# V2a.net
KiCad netlist of a schematic drawn in EAGLE
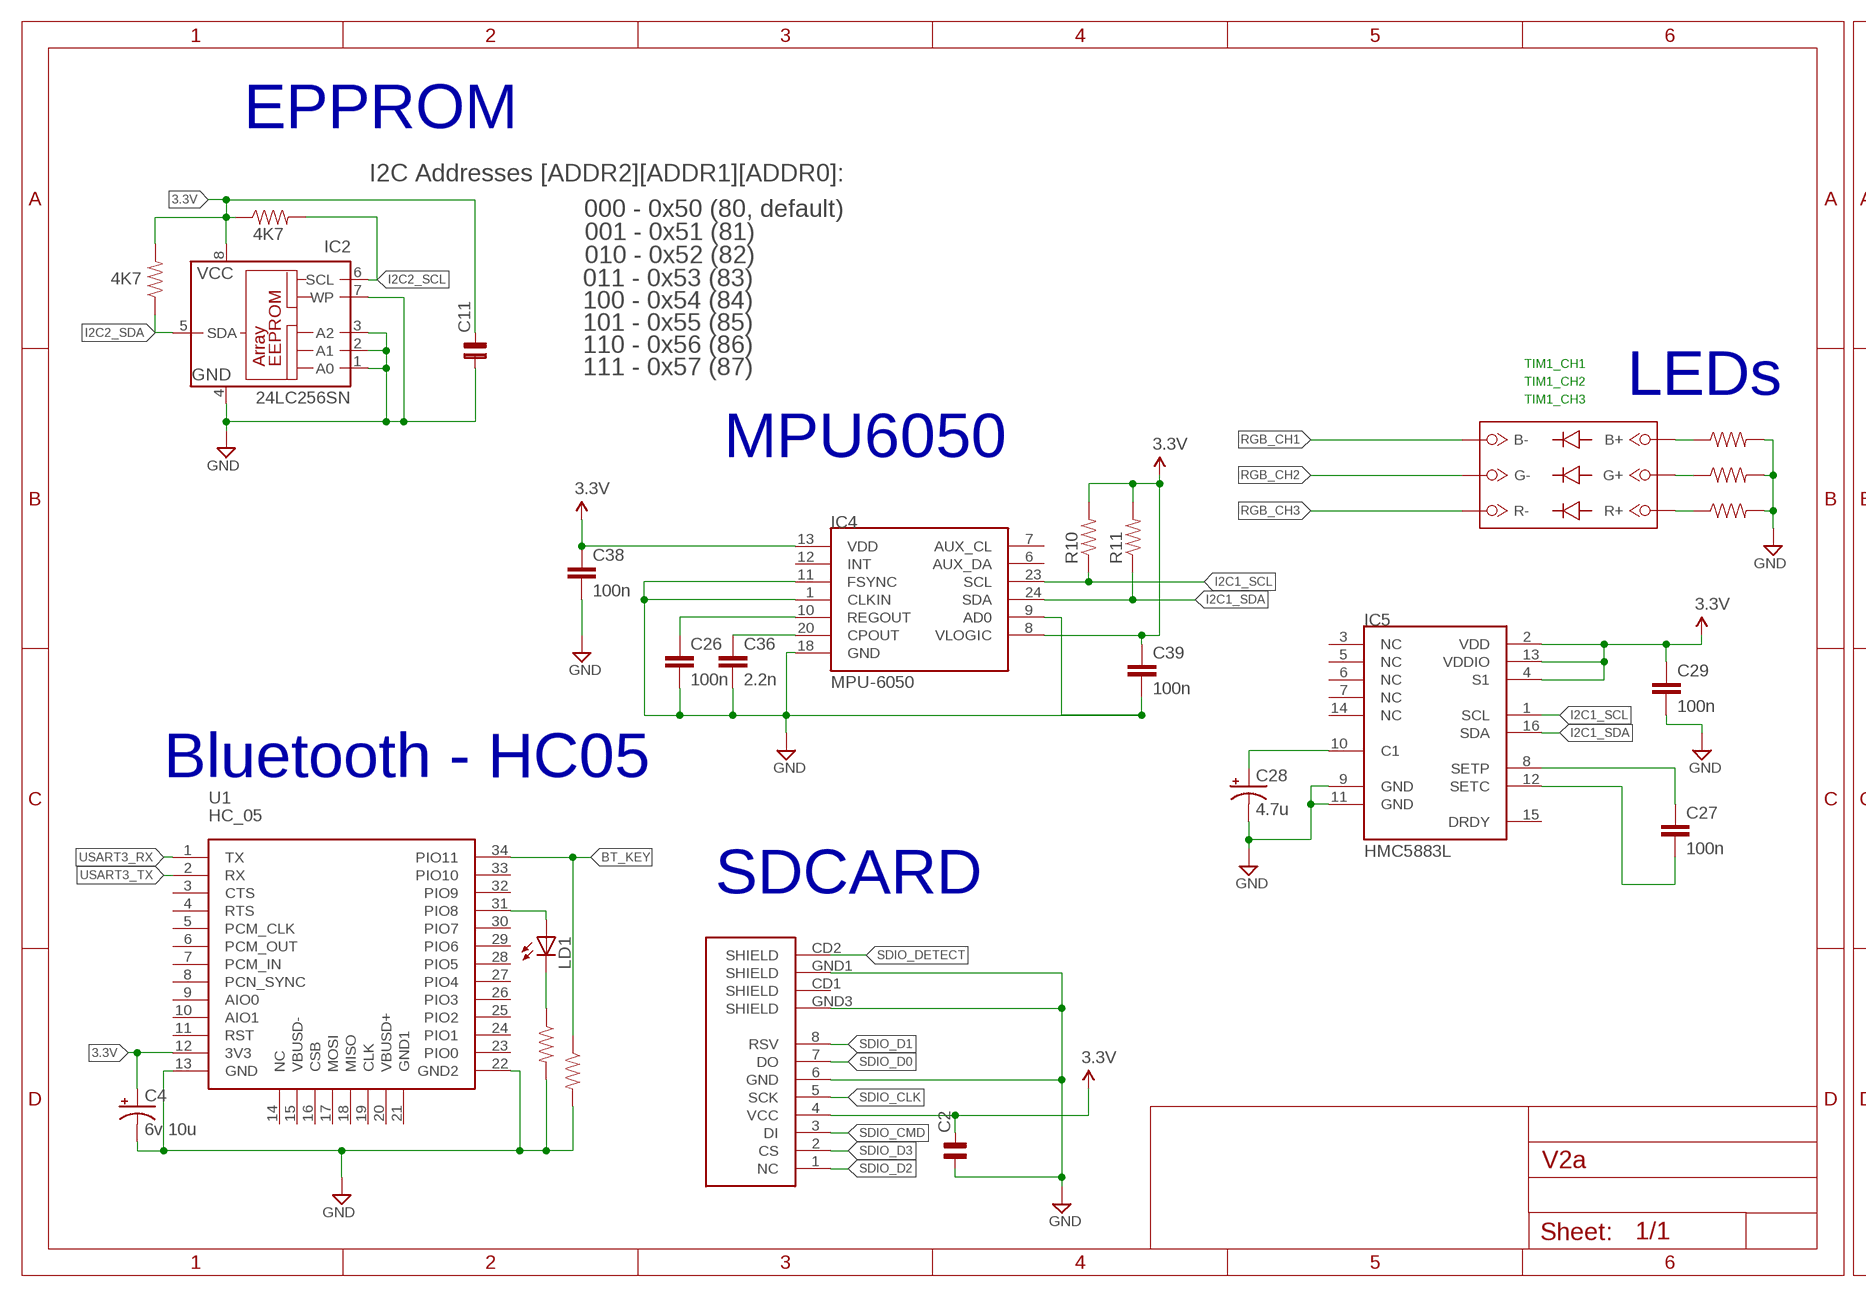
[diagram p0: schematic, sheet 1, part 1 of 2]
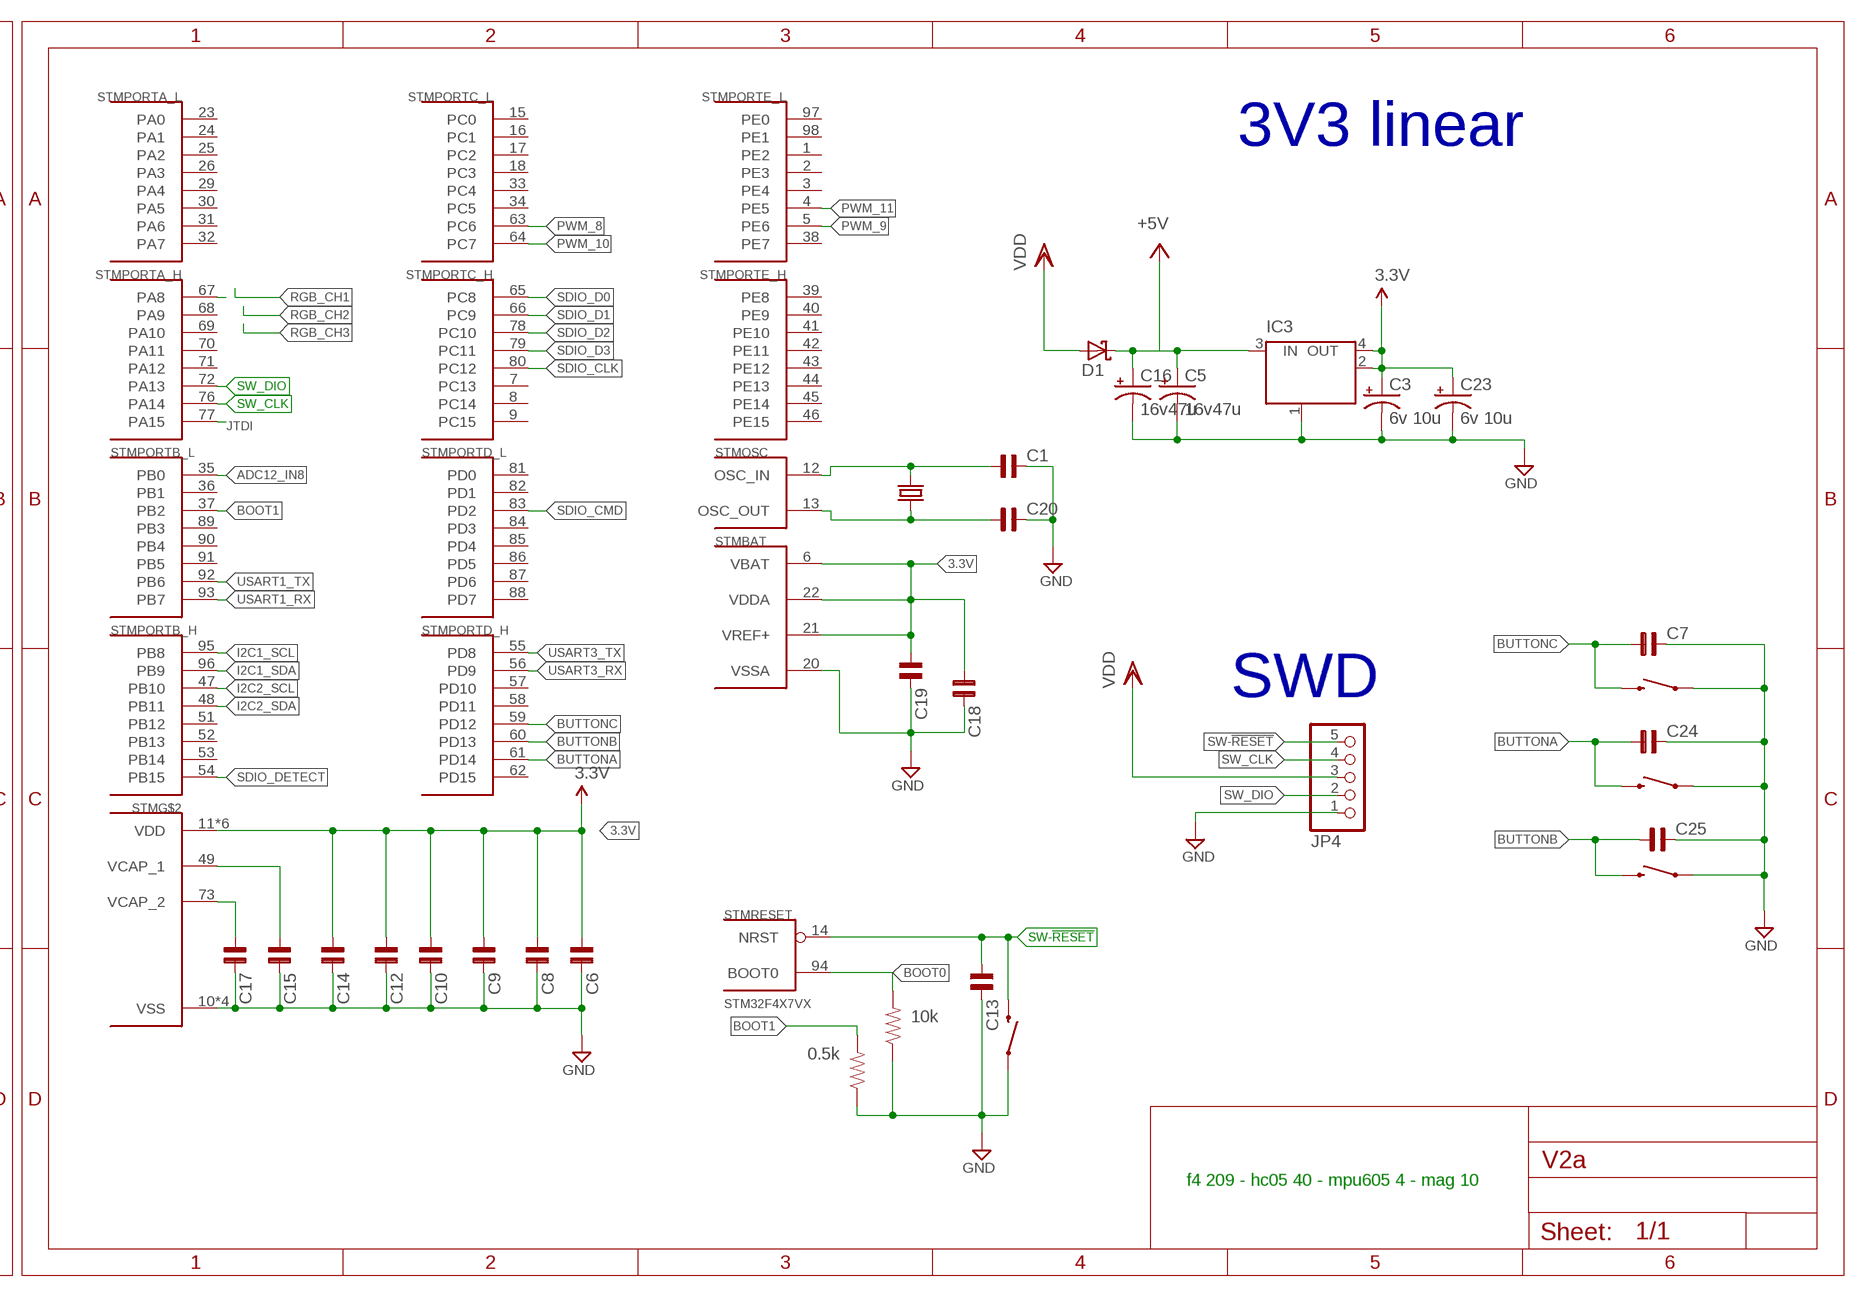
[diagram p1: schematic, sheet 1, part 2 of 2]

(export (version "E")
  (design (tool "Eeschema 10.0.6"))
  (components
    (comp (ref "C1")
      (value "C-NP-SMD-0603")
      (footprint "eagle-import:C-0603")
      (libsource (lib "eagle-import") (part "C-NP-SMD-0603"))
    )
    (comp (ref "C2")
      (value "C-NP-SMD-0603")
      (footprint "eagle-import:C-0603")
      (libsource (lib "eagle-import") (part "C-NP-SMD-0603"))
    )
    (comp (ref "C3")
      (value "6v 10u")
      (footprint "eagle-import:SMC_C")
      (libsource (lib "eagle-import") (part "CPOL-USSMCC"))
    )
    (comp (ref "C4")
      (value "6v 10u")
      (footprint "eagle-import:SMC_A")
      (libsource (lib "eagle-import") (part "CPOL-USSMCA"))
    )
    (comp (ref "C5")
      (value "16v47u")
      (footprint "eagle-import:SMC_C")
      (libsource (lib "eagle-import") (part "CPOL-USSMCC"))
    )
    (comp (ref "C6")
      (value "C-NP-SMD-0603")
      (footprint "eagle-import:C-0603")
      (libsource (lib "eagle-import") (part "C-NP-SMD-0603"))
    )
    (comp (ref "C7")
      (value "C-NP-SMD-0603")
      (footprint "eagle-import:C-0603")
      (libsource (lib "eagle-import") (part "C-NP-SMD-0603"))
    )
    (comp (ref "C8")
      (value "C-NP-SMD-0603")
      (footprint "eagle-import:C-0603")
      (libsource (lib "eagle-import") (part "C-NP-SMD-0603"))
    )
    (comp (ref "C9")
      (value "C-NP-SMD-0603")
      (footprint "eagle-import:C-0603")
      (libsource (lib "eagle-import") (part "C-NP-SMD-0603"))
    )
    (comp (ref "C10")
      (value "C-NP-SMD-0603")
      (footprint "eagle-import:C-0603")
      (libsource (lib "eagle-import") (part "C-NP-SMD-0603"))
    )
    (comp (ref "C11")
      (value "C-NP-SMD-0603")
      (footprint "eagle-import:C-0603")
      (libsource (lib "eagle-import") (part "C-NP-SMD-0603"))
    )
    (comp (ref "C12")
      (value "C-NP-SMD-0603")
      (footprint "eagle-import:C-0603")
      (libsource (lib "eagle-import") (part "C-NP-SMD-0603"))
    )
    (comp (ref "C13")
      (value "C-NP-SMD-0603")
      (footprint "eagle-import:C-0603")
      (libsource (lib "eagle-import") (part "C-NP-SMD-0603"))
    )
    (comp (ref "C14")
      (value "C-NP-SMD-0603")
      (footprint "eagle-import:C-0603")
      (libsource (lib "eagle-import") (part "C-NP-SMD-0603"))
    )
    (comp (ref "C15")
      (value "C-NP-SMD-0603")
      (footprint "eagle-import:C-0603")
      (libsource (lib "eagle-import") (part "C-NP-SMD-0603"))
    )
    (comp (ref "C16")
      (value "16v47u")
      (footprint "eagle-import:SMC_C")
      (libsource (lib "eagle-import") (part "CPOL-USSMCC"))
    )
    (comp (ref "C17")
      (value "C-NP-SMD-0603")
      (footprint "eagle-import:C-0603")
      (libsource (lib "eagle-import") (part "C-NP-SMD-0603"))
    )
    (comp (ref "C18")
      (value "C-NP-SMD-0603")
      (footprint "eagle-import:C-0603")
      (libsource (lib "eagle-import") (part "C-NP-SMD-0603"))
    )
    (comp (ref "C19")
      (value "C-NP-SMD-0603")
      (footprint "eagle-import:C-0603")
      (libsource (lib "eagle-import") (part "C-NP-SMD-0603"))
    )
    (comp (ref "C20")
      (value "C-NP-SMD-0603")
      (footprint "eagle-import:C-0603")
      (libsource (lib "eagle-import") (part "C-NP-SMD-0603"))
    )
    (comp (ref "C23")
      (value "6v 10u")
      (footprint "eagle-import:SMC_C")
      (libsource (lib "eagle-import") (part "CPOL-USSMCC"))
    )
    (comp (ref "C24")
      (value "C-NP-SMD-0603")
      (footprint "eagle-import:C-0603")
      (libsource (lib "eagle-import") (part "C-NP-SMD-0603"))
    )
    (comp (ref "C25")
      (value "C-NP-SMD-0603")
      (footprint "eagle-import:C-0603")
      (libsource (lib "eagle-import") (part "C-NP-SMD-0603"))
    )
    (comp (ref "C26")
      (value "100n")
      (footprint "eagle-import:SPARKFUN_0603-CAP")
      (libsource (lib "eagle-import") (part "SPARKFUN_CAP0603-CAP"))
    )
    (comp (ref "C27")
      (value "100n")
      (footprint "eagle-import:SPARKFUN_0603-CAP")
      (libsource (lib "eagle-import") (part "SPARKFUN_CAP0603-CAP"))
    )
    (comp (ref "C28")
      (value "4.7u")
      (footprint "eagle-import:SMC_A")
      (libsource (lib "eagle-import") (part "CPOL-USSMCA"))
    )
    (comp (ref "C29")
      (value "100n")
      (footprint "eagle-import:SPARKFUN_0603-CAP")
      (libsource (lib "eagle-import") (part "SPARKFUN_CAP0603-CAP"))
    )
    (comp (ref "C36")
      (value "2.2n")
      (footprint "eagle-import:SPARKFUN_0603-CAP")
      (libsource (lib "eagle-import") (part "SPARKFUN_CAP0603-CAP"))
    )
    (comp (ref "C38")
      (value "100n")
      (footprint "eagle-import:SPARKFUN_0603-CAP")
      (libsource (lib "eagle-import") (part "SPARKFUN_CAP0603-CAP"))
    )
    (comp (ref "C39")
      (value "100n")
      (footprint "eagle-import:SPARKFUN_0603-CAP")
      (libsource (lib "eagle-import") (part "SPARKFUN_CAP0603-CAP"))
    )
    (comp (ref "D1")
      (value "MBRS330T3")
      (footprint "eagle-import:SMC")
      (libsource (lib "eagle-import") (part "MBRS30T33"))
    )
    (comp (ref "IC2")
      (value "24LC256SN")
      (footprint "eagle-import:SO-08")
      (fields (field (name "MF") "MICROCHIP") (field (name "MPN") "24LC256-I/SN"))
      (libsource (lib "eagle-import") (part "24SNLC256"))
    )
    (comp (ref "IC3")
      (value "LINEAR_MC33269ST-3.3T3")
      (footprint "eagle-import:LINEAR_SOT223")
      (libsource (lib "eagle-import") (part "LINEAR_MC33269ST-3.3T3"))
    )
    (comp (ref "IC4")
      (value "MPU-6050")
      (footprint "eagle-import:TESTING_QFN-24-4MM2")
      (libsource (lib "eagle-import") (part "TESTING_MPU-6050-1"))
    )
    (comp (ref "IC5")
      (value "HMC5883L")
      (footprint "eagle-import:SPARKFUN_16LPCC")
      (libsource (lib "eagle-import") (part "SPARKFUN_HMC5883LSMD"))
    )
    (comp (ref "JP4")
      (value "PINHD-1X5_2.54-90°")
      (footprint "eagle-import:1X05_90")
      (libsource (lib "eagle-import") (part "PINHD-1X5_2.54-90°"))
    )
    (comp (ref "LD1")
      (value "LEDCHIPLED_0603")
      (footprint "eagle-import:CHIPLED_0603")
      (libsource (lib "eagle-import") (part "LEDCHIPLED_0603"))
    )
    (comp (ref "R2")
      (value "10K")
      (footprint "eagle-import:SPARKFUN_0603-RES")
      (libsource (lib "eagle-import") (part "Robotech_RCL_SPARKFUN_RESISTOR0603-RES"))
    )
    (comp (ref "R3")
      (value "10K")
      (footprint "eagle-import:SPARKFUN_0603-RES")
      (libsource (lib "eagle-import") (part "Robotech_RCL_SPARKFUN_RESISTOR0603-RES"))
    )
    (comp (ref "R5")
      (value "10K")
      (footprint "eagle-import:SPARKFUN_0603-RES")
      (libsource (lib "eagle-import") (part "Robotech_RCL_SPARKFUN_RESISTOR0603-RES"))
    )
    (comp (ref "R6")
      (value "10K")
      (footprint "eagle-import:SPARKFUN_0603-RES")
      (libsource (lib "eagle-import") (part "Robotech_RCL_SPARKFUN_RESISTOR0603-RES"))
    )
    (comp (ref "R7")
      (value "10k")
      (footprint "eagle-import:SPARKFUN_0603-RES")
      (libsource (lib "eagle-import") (part "Robotech_RCL_SPARKFUN_RESISTOR0603-RES"))
    )
    (comp (ref "R8")
      (value "0.5k")
      (footprint "eagle-import:SPARKFUN_0603-RES")
      (libsource (lib "eagle-import") (part "Robotech_RCL_SPARKFUN_RESISTOR0603-RES"))
    )
    (comp (ref "R9")
      (value "10K")
      (footprint "eagle-import:SPARKFUN_0603-RES")
      (libsource (lib "eagle-import") (part "Robotech_RCL_SPARKFUN_RESISTOR0603-RES"))
    )
    (comp (ref "R10")
      (value "SPARKFUN_RESISTOR0603-RES")
      (footprint "eagle-import:SPARKFUN_0603-RES")
      (libsource (lib "eagle-import") (part "SPARKFUN_RESISTOR0603-RES"))
    )
    (comp (ref "R11")
      (value "SPARKFUN_RESISTOR0603-RES")
      (footprint "eagle-import:SPARKFUN_0603-RES")
      (libsource (lib "eagle-import") (part "SPARKFUN_RESISTOR0603-RES"))
    )
    (comp (ref "R15")
      (value "4K7")
      (footprint "eagle-import:SPARKFUN_0603-RES")
      (libsource (lib "eagle-import") (part "Robotech_RCL_SPARKFUN_RESISTOR0603-RES"))
    )
    (comp (ref "R16")
      (value "4K7")
      (footprint "eagle-import:SPARKFUN_0603-RES")
      (libsource (lib "eagle-import") (part "Robotech_RCL_SPARKFUN_RESISTOR0603-RES"))
    )
    (comp (ref "S1")
      (value "RESET")
      (footprint "eagle-import:TACTILE-SWITCH-1101NE")
      (fields (field (name "PARTNO") "EVQ-P7J01P"))
      (libsource (lib "eagle-import") (part "SWITCH-MOMENTARY-2-SMD-1101NE"))
    )
    (comp (ref "S2")
      (value "RESET")
      (footprint "eagle-import:TACTILE-SWITCH-1101NE")
      (fields (field (name "PARTNO") "EVQ-P7J01P"))
      (libsource (lib "eagle-import") (part "SWITCH-MOMENTARY-2-SMD-1101NE"))
    )
    (comp (ref "S3")
      (value "RESET")
      (footprint "eagle-import:TACTILE-SWITCH-1101NE")
      (fields (field (name "PARTNO") "EVQ-P7J01P"))
      (libsource (lib "eagle-import") (part "SWITCH-MOMENTARY-2-SMD-1101NE"))
    )
    (comp (ref "S4")
      (value "RESET")
      (footprint "eagle-import:TACTILE-SWITCH-1101NE")
      (fields (field (name "PARTNO") "EVQ-P7J01P"))
      (libsource (lib "eagle-import") (part "SWITCH-MOMENTARY-2-SMD-1101NE"))
    )
    (comp (ref "SDCARD2")
      (value "microSD Socket")
      (footprint "eagle-import:MICRO-SD-SOCKET-PP")
      (libsource (lib "eagle-import") (part "USD-SOCKETNEW"))
    )
    (comp (ref "STM")
      (value "STM32F4X7VX")
      (footprint "eagle-import:TQFP100")
      (fields (field (name "PARTNO") "STM32F427VI"))
      (libsource (lib "eagle-import") (part "STM32F4X7VX"))
    )
    (comp (ref "U$12")
      (value "RGB_LED")
      (footprint "eagle-import:SMD")
      (libsource (lib "eagle-import") (part "RGB_LED"))
    )
    (comp (ref "U1")
      (value "HC_05")
      (footprint "eagle-import:BLUETOOTH_SMD")
      (libsource (lib "eagle-import") (part "HC_05"))
    )
    (comp (ref "Y1")
      (value "CRYSTALHC49US")
      (footprint "eagle-import:HC49US")
      (libsource (lib "eagle-import") (part "CRYSTALHC49US"))
    )
  )
  (nets
    (net (code "1") (name "+5V") (class "Default")
      (node (ref "C16") (pin "+") (pinfunction "+_+") (pintype "passive"))
      (node (ref "C5") (pin "+") (pinfunction "+_+") (pintype "passive"))
      (node (ref "D1") (pin "C") (pinfunction "C_C") (pintype "passive"))
      (node (ref "IC3") (pin "3") (pinfunction "IN_3") (pintype "input"))
    )
    (net (code "2") (name "/JTDI") (class "Default")
      (node (ref "STM") (pin "77") (pinfunction "PA15_77") (pintype "bidirectional"))
    )
    (net (code "3") (name "/SW-~{RESET}") (class "Default")
      (node (ref "C13") (pin "1") (pinfunction "1_1") (pintype "passive"))
      (node (ref "JP4") (pin "5") (pinfunction "5_5") (pintype "passive"))
      (node (ref "S1") (pin "P$2") (pinfunction "2_P$2") (pintype "passive"))
      (node (ref "STM") (pin "14") (pinfunction "NRST_14") (pintype "input"))
    )
    (net (code "4") (name "3.3V") (class "Default")
      (node (ref "C10") (pin "1") (pinfunction "1_1") (pintype "passive"))
      (node (ref "C11") (pin "2") (pinfunction "2_2") (pintype "passive"))
      (node (ref "C12") (pin "1") (pinfunction "1_1") (pintype "passive"))
      (node (ref "C14") (pin "1") (pinfunction "1_1") (pintype "passive"))
      (node (ref "C18") (pin "1") (pinfunction "1_1") (pintype "passive"))
      (node (ref "C19") (pin "1") (pinfunction "1_1") (pintype "passive"))
      (node (ref "C2") (pin "2") (pinfunction "2_2") (pintype "passive"))
      (node (ref "C23") (pin "+") (pinfunction "+_+") (pintype "passive"))
      (node (ref "C29") (pin "1") (pinfunction "1_1") (pintype "passive"))
      (node (ref "C3") (pin "+") (pinfunction "+_+") (pintype "passive"))
      (node (ref "C38") (pin "1") (pinfunction "1_1") (pintype "passive"))
      (node (ref "C39") (pin "1") (pinfunction "1_1") (pintype "passive"))
      (node (ref "C4") (pin "+") (pinfunction "+_+") (pintype "passive"))
      (node (ref "C6") (pin "1") (pinfunction "1_1") (pintype "passive"))
      (node (ref "C8") (pin "1") (pinfunction "1_1") (pintype "passive"))
      (node (ref "C9") (pin "1") (pinfunction "1_1") (pintype "passive"))
      (node (ref "IC2") (pin "8") (pinfunction "VCC_8") (pintype "power_in"))
      (node (ref "IC3") (pin "2") (pinfunction "OUT_2") (pintype "passive"))
      (node (ref "IC3") (pin "4") (pinfunction "OUT_4") (pintype "passive"))
      (node (ref "IC4") (pin "13") (pinfunction "VDD_13") (pintype "bidirectional"))
      (node (ref "IC4") (pin "8") (pinfunction "VLOGIC_8") (pintype "bidirectional"))
      (node (ref "IC5") (pin "13") (pinfunction "VDDIO_13") (pintype "bidirectional"))
      (node (ref "IC5") (pin "2") (pinfunction "VDD_2") (pintype "bidirectional"))
      (node (ref "IC5") (pin "4") (pinfunction "S1_4") (pintype "bidirectional"))
      (node (ref "R10") (pin "2") (pinfunction "2_2") (pintype "passive"))
      (node (ref "R11") (pin "2") (pinfunction "2_2") (pintype "passive"))
      (node (ref "R15") (pin "1") (pinfunction "1_1") (pintype "passive"))
      (node (ref "R16") (pin "2") (pinfunction "2_2") (pintype "passive"))
      (node (ref "SDCARD2") (pin "4") (pinfunction "VCC_4") (pintype "bidirectional"))
      (node (ref "STM") (pin "100") (pinfunction "VDD_100") (pintype "power_in"))
      (node (ref "STM") (pin "11") (pinfunction "VDD_11") (pintype "power_in"))
      (node (ref "STM") (pin "19") (pinfunction "VDD_19") (pintype "power_in"))
      (node (ref "STM") (pin "21") (pinfunction "VREF+_21") (pintype "input"))
      (node (ref "STM") (pin "22") (pinfunction "VDDA_22") (pintype "power_in"))
      (node (ref "STM") (pin "28") (pinfunction "VDD_28") (pintype "power_in"))
      (node (ref "STM") (pin "50") (pinfunction "VDD_50") (pintype "power_in"))
      (node (ref "STM") (pin "6") (pinfunction "VBAT_6") (pintype "power_in"))
      (node (ref "STM") (pin "75") (pinfunction "VDD_75") (pintype "power_in"))
      (node (ref "U1") (pin "12") (pinfunction "3V3_12") (pintype "bidirectional"))
    )
    (net (code "5") (name "ADC12_IN8") (class "Default")
      (node (ref "STM") (pin "35") (pinfunction "PB0_35") (pintype "bidirectional"))
    )
    (net (code "6") (name "BOOT0") (class "Default")
      (node (ref "R7") (pin "2") (pinfunction "2_2") (pintype "passive"))
      (node (ref "STM") (pin "94") (pinfunction "BOOT0_94") (pintype "input"))
    )
    (net (code "7") (name "BOOT1") (class "Default")
      (node (ref "R8") (pin "2") (pinfunction "2_2") (pintype "passive"))
      (node (ref "STM") (pin "37") (pinfunction "PB2_37") (pintype "bidirectional"))
    )
    (net (code "8") (name "BT_KEY") (class "Default")
      (node (ref "R5") (pin "1") (pinfunction "1_1") (pintype "passive"))
      (node (ref "U1") (pin "34") (pinfunction "PIO11_34") (pintype "bidirectional"))
    )
    (net (code "9") (name "BUTTONA") (class "Default")
      (node (ref "C24") (pin "1") (pinfunction "1_1") (pintype "passive"))
      (node (ref "S3") (pin "P$2") (pinfunction "2_P$2") (pintype "passive"))
      (node (ref "STM") (pin "61") (pinfunction "PD14_61") (pintype "bidirectional"))
    )
    (net (code "10") (name "BUTTONB") (class "Default")
      (node (ref "C25") (pin "1") (pinfunction "1_1") (pintype "passive"))
      (node (ref "S2") (pin "P$2") (pinfunction "2_P$2") (pintype "passive"))
      (node (ref "STM") (pin "60") (pinfunction "PD13_60") (pintype "bidirectional"))
    )
    (net (code "11") (name "BUTTONC") (class "Default")
      (node (ref "C7") (pin "1") (pinfunction "1_1") (pintype "passive"))
      (node (ref "S4") (pin "P$2") (pinfunction "2_P$2") (pintype "passive"))
      (node (ref "STM") (pin "59") (pinfunction "PD12_59") (pintype "bidirectional"))
    )
    (net (code "12") (name "GND") (class "Default")
      (node (ref "C1") (pin "2") (pinfunction "2_2") (pintype "passive"))
      (node (ref "C10") (pin "2") (pinfunction "2_2") (pintype "passive"))
      (node (ref "C11") (pin "1") (pinfunction "1_1") (pintype "passive"))
      (node (ref "C12") (pin "2") (pinfunction "2_2") (pintype "passive"))
      (node (ref "C13") (pin "2") (pinfunction "2_2") (pintype "passive"))
      (node (ref "C14") (pin "2") (pinfunction "2_2") (pintype "passive"))
      (node (ref "C15") (pin "2") (pinfunction "2_2") (pintype "passive"))
      (node (ref "C16") (pin "-") (pinfunction "-_-") (pintype "passive"))
      (node (ref "C17") (pin "2") (pinfunction "2_2") (pintype "passive"))
      (node (ref "C18") (pin "2") (pinfunction "2_2") (pintype "passive"))
      (node (ref "C19") (pin "2") (pinfunction "2_2") (pintype "passive"))
      (node (ref "C2") (pin "1") (pinfunction "1_1") (pintype "passive"))
      (node (ref "C20") (pin "2") (pinfunction "2_2") (pintype "passive"))
      (node (ref "C23") (pin "-") (pinfunction "-_-") (pintype "passive"))
      (node (ref "C24") (pin "2") (pinfunction "2_2") (pintype "passive"))
      (node (ref "C25") (pin "2") (pinfunction "2_2") (pintype "passive"))
      (node (ref "C26") (pin "2") (pinfunction "2_2") (pintype "passive"))
      (node (ref "C28") (pin "-") (pinfunction "-_-") (pintype "passive"))
      (node (ref "C29") (pin "2") (pinfunction "2_2") (pintype "passive"))
      (node (ref "C3") (pin "-") (pinfunction "-_-") (pintype "passive"))
      (node (ref "C36") (pin "2") (pinfunction "2_2") (pintype "passive"))
      (node (ref "C38") (pin "2") (pinfunction "2_2") (pintype "passive"))
      (node (ref "C39") (pin "2") (pinfunction "2_2") (pintype "passive"))
      (node (ref "C4") (pin "-") (pinfunction "-_-") (pintype "passive"))
      (node (ref "C5") (pin "-") (pinfunction "-_-") (pintype "passive"))
      (node (ref "C6") (pin "2") (pinfunction "2_2") (pintype "passive"))
      (node (ref "C7") (pin "2") (pinfunction "2_2") (pintype "passive"))
      (node (ref "C8") (pin "2") (pinfunction "2_2") (pintype "passive"))
      (node (ref "C9") (pin "2") (pinfunction "2_2") (pintype "passive"))
      (node (ref "IC2") (pin "1") (pinfunction "A0_1") (pintype "input"))
      (node (ref "IC2") (pin "2") (pinfunction "A1_2") (pintype "input"))
      (node (ref "IC2") (pin "3") (pinfunction "A2_3") (pintype "input"))
      (node (ref "IC2") (pin "4") (pinfunction "GND_4") (pintype "power_in"))
      (node (ref "IC2") (pin "7") (pinfunction "WP_7") (pintype "input"))
      (node (ref "IC3") (pin "1") (pinfunction "GND/ADJ_1") (pintype "input"))
      (node (ref "IC4") (pin "1") (pinfunction "CLKIN_1") (pintype "bidirectional"))
      (node (ref "IC4") (pin "11") (pinfunction "FSYNC_11") (pintype "bidirectional"))
      (node (ref "IC4") (pin "18") (pinfunction "GND_18") (pintype "bidirectional"))
      (node (ref "IC4") (pin "9") (pinfunction "AD0_9") (pintype "bidirectional"))
      (node (ref "IC5") (pin "11") (pinfunction "GND_11") (pintype "bidirectional"))
      (node (ref "IC5") (pin "9") (pinfunction "GND_9") (pintype "bidirectional"))
      (node (ref "JP4") (pin "1") (pinfunction "1_1") (pintype "passive"))
      (node (ref "R2") (pin "2") (pinfunction "2_2") (pintype "passive"))
      (node (ref "R3") (pin "2") (pinfunction "2_2") (pintype "passive"))
      (node (ref "R5") (pin "2") (pinfunction "2_2") (pintype "passive"))
      (node (ref "R6") (pin "2") (pinfunction "2_2") (pintype "passive"))
      (node (ref "R7") (pin "1") (pinfunction "1_1") (pintype "passive"))
      (node (ref "R8") (pin "1") (pinfunction "1_1") (pintype "passive"))
      (node (ref "R9") (pin "2") (pinfunction "2_2") (pintype "passive"))
      (node (ref "S1") (pin "P$1") (pinfunction "1_P$1") (pintype "passive"))
      (node (ref "S2") (pin "P$1") (pinfunction "1_P$1") (pintype "passive"))
      (node (ref "S3") (pin "P$1") (pinfunction "1_P$1") (pintype "passive"))
      (node (ref "S4") (pin "P$1") (pinfunction "1_P$1") (pintype "passive"))
      (node (ref "SDCARD2") (pin "6") (pinfunction "GND_6") (pintype "bidirectional"))
      (node (ref "SDCARD2") (pin "GND1") (pinfunction "SHIELD_GND1") (pintype "bidirectional"))
      (node (ref "SDCARD2") (pin "GND3") (pinfunction "SHIELD_GND3") (pintype "bidirectional"))
      (node (ref "STM") (pin "10") (pinfunction "VSS_10") (pintype "power_in"))
      (node (ref "STM") (pin "20") (pinfunction "VSSA_20") (pintype "power_in"))
      (node (ref "STM") (pin "27") (pinfunction "VSS_27") (pintype "power_in"))
      (node (ref "STM") (pin "74") (pinfunction "VSS_74") (pintype "power_in"))
      (node (ref "STM") (pin "99") (pinfunction "VSS_99") (pintype "power_in"))
      (node (ref "U1") (pin "13") (pinfunction "GND_13") (pintype "bidirectional"))
      (node (ref "U1") (pin "22") (pinfunction "GND2_22") (pintype "bidirectional"))
    )
    (net (code "13") (name "I2C1_SCL") (class "Default")
      (node (ref "IC4") (pin "23") (pinfunction "SCL_23") (pintype "bidirectional"))
      (node (ref "IC5") (pin "1") (pinfunction "SCL_1") (pintype "bidirectional"))
      (node (ref "R10") (pin "1") (pinfunction "1_1") (pintype "passive"))
      (node (ref "STM") (pin "95") (pinfunction "PB8_95") (pintype "bidirectional"))
    )
    (net (code "14") (name "I2C1_SDA") (class "Default")
      (node (ref "IC4") (pin "24") (pinfunction "SDA_24") (pintype "bidirectional"))
      (node (ref "IC5") (pin "16") (pinfunction "SDA_16") (pintype "bidirectional"))
      (node (ref "R11") (pin "1") (pinfunction "1_1") (pintype "passive"))
      (node (ref "STM") (pin "96") (pinfunction "PB9_96") (pintype "bidirectional"))
    )
    (net (code "15") (name "I2C2_SCL") (class "Default")
      (node (ref "IC2") (pin "6") (pinfunction "SCL_6") (pintype "input"))
      (node (ref "R15") (pin "2") (pinfunction "2_2") (pintype "passive"))
      (node (ref "STM") (pin "47") (pinfunction "PB10_47") (pintype "bidirectional"))
    )
    (net (code "16") (name "I2C2_SDA") (class "Default")
      (node (ref "IC2") (pin "5") (pinfunction "SDA_5") (pintype "bidirectional"))
      (node (ref "R16") (pin "1") (pinfunction "1_1") (pintype "passive"))
      (node (ref "STM") (pin "48") (pinfunction "PB11_48") (pintype "bidirectional"))
    )
    (net (code "17") (name "Net-(IC4-CPOUT)") (class "Default")
      (node (ref "C36") (pin "1") (pinfunction "1_1") (pintype "passive"))
      (node (ref "IC4") (pin "20") (pinfunction "CPOUT_20") (pintype "bidirectional"))
    )
    (net (code "18") (name "Net-(IC4-REGOUT)") (class "Default")
      (node (ref "C26") (pin "1") (pinfunction "1_1") (pintype "passive"))
      (node (ref "IC4") (pin "10") (pinfunction "REGOUT_10") (pintype "bidirectional"))
    )
    (net (code "19") (name "Net-(IC5-C1)") (class "Default")
      (node (ref "C28") (pin "+") (pinfunction "+_+") (pintype "passive"))
      (node (ref "IC5") (pin "10") (pinfunction "C1_10") (pintype "bidirectional"))
    )
    (net (code "20") (name "Net-(IC5-SETC)") (class "Default")
      (node (ref "C27") (pin "2") (pinfunction "2_2") (pintype "passive"))
      (node (ref "IC5") (pin "12") (pinfunction "SETC_12") (pintype "bidirectional"))
    )
    (net (code "21") (name "Net-(IC5-SETP)") (class "Default")
      (node (ref "C27") (pin "1") (pinfunction "1_1") (pintype "passive"))
      (node (ref "IC5") (pin "8") (pinfunction "SETP_8") (pintype "bidirectional"))
    )
    (net (code "22") (name "Net-(LD1-PadC)") (class "Default")
      (node (ref "LD1") (pin "C") (pinfunction "C_C") (pintype "passive"))
      (node (ref "R9") (pin "1") (pinfunction "1_1") (pintype "passive"))
    )
    (net (code "23") (name "Net-(R2-Pad1)") (class "Default")
      (node (ref "R2") (pin "1") (pinfunction "1_1") (pintype "passive"))
      (node (ref "U$12") (pin "B+") (pinfunction "B+_B+") (pintype "bidirectional"))
    )
    (net (code "24") (name "Net-(R3-Pad1)") (class "Default")
      (node (ref "R3") (pin "1") (pinfunction "1_1") (pintype "passive"))
      (node (ref "U$12") (pin "G+") (pinfunction "G+_G+") (pintype "bidirectional"))
    )
    (net (code "25") (name "Net-(R6-Pad1)") (class "Default")
      (node (ref "R6") (pin "1") (pinfunction "1_1") (pintype "passive"))
      (node (ref "U$12") (pin "R+") (pinfunction "R+_R+") (pintype "bidirectional"))
    )
    (net (code "26") (name "Net-(STMB-VCAP_1)") (class "Default")
      (node (ref "C15") (pin "1") (pinfunction "1_1") (pintype "passive"))
      (node (ref "STM") (pin "49") (pinfunction "VCAP_1_49") (pintype "power_in"))
    )
    (net (code "27") (name "Net-(STMB-VCAP_2)") (class "Default")
      (node (ref "C17") (pin "1") (pinfunction "1_1") (pintype "passive"))
      (node (ref "STM") (pin "73") (pinfunction "VCAP_2_73") (pintype "power_in"))
    )
    (net (code "28") (name "Net-(STMC-OSC_IN)") (class "Default")
      (node (ref "C1") (pin "1") (pinfunction "1_1") (pintype "passive"))
      (node (ref "STM") (pin "12") (pinfunction "OSC_IN_12") (pintype "input"))
      (node (ref "Y1") (pin "2") (pinfunction "2_2") (pintype "passive"))
    )
    (net (code "29") (name "Net-(STMC-OSC_OUT)") (class "Default")
      (node (ref "C20") (pin "1") (pinfunction "1_1") (pintype "passive"))
      (node (ref "STM") (pin "13") (pinfunction "OSC_OUT_13") (pintype "output"))
      (node (ref "Y1") (pin "1") (pinfunction "1_1") (pintype "passive"))
    )
    (net (code "30") (name "Net-(U1-PIO8)") (class "Default")
      (node (ref "LD1") (pin "A") (pinfunction "A_A") (pintype "passive"))
      (node (ref "U1") (pin "31") (pinfunction "PIO8_31") (pintype "bidirectional"))
    )
    (net (code "31") (name "PWM_8") (class "Default")
      (node (ref "STM") (pin "63") (pinfunction "PC6_63") (pintype "bidirectional"))
    )
    (net (code "32") (name "PWM_9") (class "Default")
      (node (ref "STM") (pin "5") (pinfunction "PE6_5") (pintype "bidirectional"))
    )
    (net (code "33") (name "PWM_10") (class "Default")
      (node (ref "STM") (pin "64") (pinfunction "PC7_64") (pintype "bidirectional"))
    )
    (net (code "34") (name "PWM_11") (class "Default")
      (node (ref "STM") (pin "4") (pinfunction "PE5_4") (pintype "bidirectional"))
    )
    (net (code "35") (name "RGB_CH1") (class "Default")
      (node (ref "U$12") (pin "B-") (pinfunction "B-_B-") (pintype "bidirectional"))
    )
    (net (code "36") (name "RGB_CH2") (class "Default")
      (node (ref "U$12") (pin "G-") (pinfunction "G-_G-") (pintype "bidirectional"))
    )
    (net (code "37") (name "RGB_CH3") (class "Default")
      (node (ref "U$12") (pin "R-") (pinfunction "R-_R-") (pintype "bidirectional"))
    )
    (net (code "38") (name "SDIO_CLK") (class "Default")
      (node (ref "SDCARD2") (pin "5") (pinfunction "SCK_5") (pintype "bidirectional"))
      (node (ref "STM") (pin "80") (pinfunction "PC12_80") (pintype "bidirectional"))
    )
    (net (code "39") (name "SDIO_CMD") (class "Default")
      (node (ref "SDCARD2") (pin "3") (pinfunction "DI_3") (pintype "bidirectional"))
      (node (ref "STM") (pin "83") (pinfunction "PD2_83") (pintype "bidirectional"))
    )
    (net (code "40") (name "SDIO_D0") (class "Default")
      (node (ref "SDCARD2") (pin "7") (pinfunction "DO_7") (pintype "bidirectional"))
      (node (ref "STM") (pin "65") (pinfunction "PC8_65") (pintype "bidirectional"))
    )
    (net (code "41") (name "SDIO_D1") (class "Default")
      (node (ref "SDCARD2") (pin "8") (pinfunction "RSV_8") (pintype "bidirectional"))
      (node (ref "STM") (pin "66") (pinfunction "PC9_66") (pintype "bidirectional"))
    )
    (net (code "42") (name "SDIO_D2") (class "Default")
      (node (ref "SDCARD2") (pin "1") (pinfunction "NC_1") (pintype "bidirectional"))
      (node (ref "STM") (pin "78") (pinfunction "PC10_78") (pintype "bidirectional"))
    )
    (net (code "43") (name "SDIO_D3") (class "Default")
      (node (ref "SDCARD2") (pin "2") (pinfunction "CS_2") (pintype "bidirectional"))
      (node (ref "STM") (pin "79") (pinfunction "PC11_79") (pintype "bidirectional"))
    )
    (net (code "44") (name "SDIO_DETECT") (class "Default")
      (node (ref "SDCARD2") (pin "CD2") (pinfunction "SHIELD_CD2") (pintype "bidirectional"))
      (node (ref "STM") (pin "54") (pinfunction "PB15_54") (pintype "bidirectional"))
    )
    (net (code "45") (name "SW_CLK") (class "Default")
      (node (ref "JP4") (pin "4") (pinfunction "4_4") (pintype "passive"))
      (node (ref "STM") (pin "76") (pinfunction "PA14_76") (pintype "bidirectional"))
    )
    (net (code "46") (name "SW_DIO") (class "Default")
      (node (ref "JP4") (pin "2") (pinfunction "2_2") (pintype "passive"))
      (node (ref "STM") (pin "72") (pinfunction "PA13_72") (pintype "bidirectional"))
    )
    (net (code "47") (name "USART1_RX") (class "Default")
      (node (ref "STM") (pin "93") (pinfunction "PB7_93") (pintype "bidirectional"))
    )
    (net (code "48") (name "USART1_TX") (class "Default")
      (node (ref "STM") (pin "92") (pinfunction "PB6_92") (pintype "bidirectional"))
    )
    (net (code "49") (name "USART3_RX") (class "Default")
      (node (ref "STM") (pin "56") (pinfunction "PD9_56") (pintype "bidirectional"))
      (node (ref "U1") (pin "1") (pinfunction "TX_1") (pintype "bidirectional"))
    )
    (net (code "50") (name "USART3_TX") (class "Default")
      (node (ref "STM") (pin "55") (pinfunction "PD8_55") (pintype "bidirectional"))
      (node (ref "U1") (pin "2") (pinfunction "RX_2") (pintype "bidirectional"))
    )
    (net (code "51") (name "VDD") (class "Default")
      (node (ref "D1") (pin "A") (pinfunction "A_A") (pintype "passive"))
      (node (ref "JP4") (pin "3") (pinfunction "3_3") (pintype "passive"))
    )
    (net (code "52") (name "unconnected-(IC4-AUX_CL-Pad7)") (class "Default")
      (node (ref "IC4") (pin "7") (pinfunction "AUX_CL_7") (pintype "bidirectional"))
    )
    (net (code "53") (name "unconnected-(IC4-AUX_DA-Pad6)") (class "Default")
      (node (ref "IC4") (pin "6") (pinfunction "AUX_DA_6") (pintype "bidirectional"))
    )
    (net (code "54") (name "unconnected-(IC4-INT-Pad12)") (class "Default")
      (node (ref "IC4") (pin "12") (pinfunction "INT_12") (pintype "bidirectional"))
    )
    (net (code "55") (name "unconnected-(IC5-DRDY-Pad15)") (class "Default")
      (node (ref "IC5") (pin "15") (pinfunction "DRDY_15") (pintype "bidirectional"))
    )
    (net (code "56") (name "unconnected-(IC5-NC-Pad3)") (class "Default")
      (node (ref "IC5") (pin "3") (pinfunction "NC_3") (pintype "bidirectional"))
    )
    (net (code "57") (name "unconnected-(IC5-NC-Pad5)") (class "Default")
      (node (ref "IC5") (pin "5") (pinfunction "NC_5") (pintype "bidirectional"))
    )
    (net (code "58") (name "unconnected-(IC5-NC-Pad6)") (class "Default")
      (node (ref "IC5") (pin "6") (pinfunction "NC_6") (pintype "bidirectional"))
    )
    (net (code "59") (name "unconnected-(IC5-NC-Pad7)") (class "Default")
      (node (ref "IC5") (pin "7") (pinfunction "NC_7") (pintype "bidirectional"))
    )
    (net (code "60") (name "unconnected-(IC5-NC-Pad14)") (class "Default")
      (node (ref "IC5") (pin "14") (pinfunction "NC_14") (pintype "bidirectional"))
    )
    (net (code "61") (name "unconnected-(SDCARD2-SHIELD-PadCD1)") (class "Default")
      (node (ref "SDCARD2") (pin "CD1") (pinfunction "SHIELD_CD1") (pintype "bidirectional"))
    )
    (net (code "62") (name "unconnected-(STMD-PA8-Pad67)") (class "Default")
      (node (ref "STM") (pin "67") (pinfunction "PA8_67") (pintype "bidirectional"))
    )
    (net (code "63") (name "unconnected-(STMD-PA9-Pad68)") (class "Default")
      (node (ref "STM") (pin "68") (pinfunction "PA9_68") (pintype "bidirectional"))
    )
    (net (code "64") (name "unconnected-(STMD-PA10-Pad69)") (class "Default")
      (node (ref "STM") (pin "69") (pinfunction "PA10_69") (pintype "bidirectional"))
    )
    (net (code "65") (name "unconnected-(STMD-PA11-Pad70)") (class "Default")
      (node (ref "STM") (pin "70") (pinfunction "PA11_70") (pintype "bidirectional"))
    )
    (net (code "66") (name "unconnected-(STMD-PA12-Pad71)") (class "Default")
      (node (ref "STM") (pin "71") (pinfunction "PA12_71") (pintype "bidirectional"))
    )
    (net (code "67") (name "unconnected-(STME-PA0-Pad23)") (class "Default")
      (node (ref "STM") (pin "23") (pinfunction "PA0_23") (pintype "bidirectional"))
    )
    (net (code "68") (name "unconnected-(STME-PA1-Pad24)") (class "Default")
      (node (ref "STM") (pin "24") (pinfunction "PA1_24") (pintype "bidirectional"))
    )
    (net (code "69") (name "unconnected-(STME-PA2-Pad25)") (class "Default")
      (node (ref "STM") (pin "25") (pinfunction "PA2_25") (pintype "bidirectional"))
    )
    (net (code "70") (name "unconnected-(STME-PA3-Pad26)") (class "Default")
      (node (ref "STM") (pin "26") (pinfunction "PA3_26") (pintype "bidirectional"))
    )
    (net (code "71") (name "unconnected-(STME-PA4-Pad29)") (class "Default")
      (node (ref "STM") (pin "29") (pinfunction "PA4_29") (pintype "bidirectional"))
    )
    (net (code "72") (name "unconnected-(STME-PA5-Pad30)") (class "Default")
      (node (ref "STM") (pin "30") (pinfunction "PA5_30") (pintype "bidirectional"))
    )
    (net (code "73") (name "unconnected-(STME-PA6-Pad31)") (class "Default")
      (node (ref "STM") (pin "31") (pinfunction "PA6_31") (pintype "bidirectional"))
    )
    (net (code "74") (name "unconnected-(STME-PA7-Pad32)") (class "Default")
      (node (ref "STM") (pin "32") (pinfunction "PA7_32") (pintype "bidirectional"))
    )
    (net (code "75") (name "unconnected-(STMF-PB12-Pad51)") (class "Default")
      (node (ref "STM") (pin "51") (pinfunction "PB12_51") (pintype "bidirectional"))
    )
    (net (code "76") (name "unconnected-(STMF-PB13-Pad52)") (class "Default")
      (node (ref "STM") (pin "52") (pinfunction "PB13_52") (pintype "bidirectional"))
    )
    (net (code "77") (name "unconnected-(STMF-PB14-Pad53)") (class "Default")
      (node (ref "STM") (pin "53") (pinfunction "PB14_53") (pintype "bidirectional"))
    )
    (net (code "78") (name "unconnected-(STMG-PB1-Pad36)") (class "Default")
      (node (ref "STM") (pin "36") (pinfunction "PB1_36") (pintype "bidirectional"))
    )
    (net (code "79") (name "unconnected-(STMG-PB3-Pad89)") (class "Default")
      (node (ref "STM") (pin "89") (pinfunction "PB3_89") (pintype "bidirectional"))
    )
    (net (code "80") (name "unconnected-(STMG-PB4-Pad90)") (class "Default")
      (node (ref "STM") (pin "90") (pinfunction "PB4_90") (pintype "bidirectional"))
    )
    (net (code "81") (name "unconnected-(STMG-PB5-Pad91)") (class "Default")
      (node (ref "STM") (pin "91") (pinfunction "PB5_91") (pintype "bidirectional"))
    )
    (net (code "82") (name "unconnected-(STMH-PC13-Pad7)") (class "Default")
      (node (ref "STM") (pin "7") (pinfunction "PC13_7") (pintype "bidirectional"))
    )
    (net (code "83") (name "unconnected-(STMH-PC14-Pad8)") (class "Default")
      (node (ref "STM") (pin "8") (pinfunction "PC14_8") (pintype "bidirectional"))
    )
    (net (code "84") (name "unconnected-(STMH-PC15-Pad9)") (class "Default")
      (node (ref "STM") (pin "9") (pinfunction "PC15_9") (pintype "bidirectional"))
    )
    (net (code "85") (name "unconnected-(STMI-PC0-Pad15)") (class "Default")
      (node (ref "STM") (pin "15") (pinfunction "PC0_15") (pintype "bidirectional"))
    )
    (net (code "86") (name "unconnected-(STMI-PC1-Pad16)") (class "Default")
      (node (ref "STM") (pin "16") (pinfunction "PC1_16") (pintype "bidirectional"))
    )
    (net (code "87") (name "unconnected-(STMI-PC2-Pad17)") (class "Default")
      (node (ref "STM") (pin "17") (pinfunction "PC2_17") (pintype "bidirectional"))
    )
    (net (code "88") (name "unconnected-(STMI-PC3-Pad18)") (class "Default")
      (node (ref "STM") (pin "18") (pinfunction "PC3_18") (pintype "bidirectional"))
    )
    (net (code "89") (name "unconnected-(STMI-PC4-Pad33)") (class "Default")
      (node (ref "STM") (pin "33") (pinfunction "PC4_33") (pintype "bidirectional"))
    )
    (net (code "90") (name "unconnected-(STMI-PC5-Pad34)") (class "Default")
      (node (ref "STM") (pin "34") (pinfunction "PC5_34") (pintype "bidirectional"))
    )
    (net (code "91") (name "unconnected-(STMJ-PD10-Pad57)") (class "Default")
      (node (ref "STM") (pin "57") (pinfunction "PD10_57") (pintype "bidirectional"))
    )
    (net (code "92") (name "unconnected-(STMJ-PD11-Pad58)") (class "Default")
      (node (ref "STM") (pin "58") (pinfunction "PD11_58") (pintype "bidirectional"))
    )
    (net (code "93") (name "unconnected-(STMJ-PD15-Pad62)") (class "Default")
      (node (ref "STM") (pin "62") (pinfunction "PD15_62") (pintype "bidirectional"))
    )
    (net (code "94") (name "unconnected-(STMK-PD0-Pad81)") (class "Default")
      (node (ref "STM") (pin "81") (pinfunction "PD0_81") (pintype "bidirectional"))
    )
    (net (code "95") (name "unconnected-(STMK-PD1-Pad82)") (class "Default")
      (node (ref "STM") (pin "82") (pinfunction "PD1_82") (pintype "bidirectional"))
    )
    (net (code "96") (name "unconnected-(STMK-PD3-Pad84)") (class "Default")
      (node (ref "STM") (pin "84") (pinfunction "PD3_84") (pintype "bidirectional"))
    )
    (net (code "97") (name "unconnected-(STMK-PD4-Pad85)") (class "Default")
      (node (ref "STM") (pin "85") (pinfunction "PD4_85") (pintype "bidirectional"))
    )
    (net (code "98") (name "unconnected-(STMK-PD5-Pad86)") (class "Default")
      (node (ref "STM") (pin "86") (pinfunction "PD5_86") (pintype "bidirectional"))
    )
    (net (code "99") (name "unconnected-(STMK-PD6-Pad87)") (class "Default")
      (node (ref "STM") (pin "87") (pinfunction "PD6_87") (pintype "bidirectional"))
    )
    (net (code "100") (name "unconnected-(STMK-PD7-Pad88)") (class "Default")
      (node (ref "STM") (pin "88") (pinfunction "PD7_88") (pintype "bidirectional"))
    )
    (net (code "101") (name "unconnected-(STML-PE8-Pad39)") (class "Default")
      (node (ref "STM") (pin "39") (pinfunction "PE8_39") (pintype "bidirectional"))
    )
    (net (code "102") (name "unconnected-(STML-PE9-Pad40)") (class "Default")
      (node (ref "STM") (pin "40") (pinfunction "PE9_40") (pintype "bidirectional"))
    )
    (net (code "103") (name "unconnected-(STML-PE10-Pad41)") (class "Default")
      (node (ref "STM") (pin "41") (pinfunction "PE10_41") (pintype "bidirectional"))
    )
    (net (code "104") (name "unconnected-(STML-PE11-Pad42)") (class "Default")
      (node (ref "STM") (pin "42") (pinfunction "PE11_42") (pintype "bidirectional"))
    )
    (net (code "105") (name "unconnected-(STML-PE12-Pad43)") (class "Default")
      (node (ref "STM") (pin "43") (pinfunction "PE12_43") (pintype "bidirectional"))
    )
    (net (code "106") (name "unconnected-(STML-PE13-Pad44)") (class "Default")
      (node (ref "STM") (pin "44") (pinfunction "PE13_44") (pintype "bidirectional"))
    )
    (net (code "107") (name "unconnected-(STML-PE14-Pad45)") (class "Default")
      (node (ref "STM") (pin "45") (pinfunction "PE14_45") (pintype "bidirectional"))
    )
    (net (code "108") (name "unconnected-(STML-PE15-Pad46)") (class "Default")
      (node (ref "STM") (pin "46") (pinfunction "PE15_46") (pintype "bidirectional"))
    )
    (net (code "109") (name "unconnected-(STMM-PE0-Pad97)") (class "Default")
      (node (ref "STM") (pin "97") (pinfunction "PE0_97") (pintype "bidirectional"))
    )
    (net (code "110") (name "unconnected-(STMM-PE1-Pad98)") (class "Default")
      (node (ref "STM") (pin "98") (pinfunction "PE1_98") (pintype "bidirectional"))
    )
    (net (code "111") (name "unconnected-(STMM-PE2-Pad1)") (class "Default")
      (node (ref "STM") (pin "1") (pinfunction "PE2_1") (pintype "bidirectional"))
    )
    (net (code "112") (name "unconnected-(STMM-PE3-Pad2)") (class "Default")
      (node (ref "STM") (pin "2") (pinfunction "PE3_2") (pintype "bidirectional"))
    )
    (net (code "113") (name "unconnected-(STMM-PE4-Pad3)") (class "Default")
      (node (ref "STM") (pin "3") (pinfunction "PE4_3") (pintype "bidirectional"))
    )
    (net (code "114") (name "unconnected-(STMM-PE7-Pad38)") (class "Default")
      (node (ref "STM") (pin "38") (pinfunction "PE7_38") (pintype "bidirectional"))
    )
    (net (code "115") (name "unconnected-(U1-AIO0-Pad9)") (class "Default")
      (node (ref "U1") (pin "9") (pinfunction "AIO0_9") (pintype "bidirectional"))
    )
    (net (code "116") (name "unconnected-(U1-AIO1-Pad10)") (class "Default")
      (node (ref "U1") (pin "10") (pinfunction "AIO1_10") (pintype "bidirectional"))
    )
    (net (code "117") (name "unconnected-(U1-CLK-Pad19)") (class "Default")
      (node (ref "U1") (pin "19") (pinfunction "CLK_19") (pintype "bidirectional"))
    )
    (net (code "118") (name "unconnected-(U1-CSB-Pad16)") (class "Default")
      (node (ref "U1") (pin "16") (pinfunction "CSB_16") (pintype "bidirectional"))
    )
    (net (code "119") (name "unconnected-(U1-CTS-Pad3)") (class "Default")
      (node (ref "U1") (pin "3") (pinfunction "CTS_3") (pintype "bidirectional"))
    )
    (net (code "120") (name "unconnected-(U1-GND1-Pad21)") (class "Default")
      (node (ref "U1") (pin "21") (pinfunction "GND1_21") (pintype "bidirectional"))
    )
    (net (code "121") (name "unconnected-(U1-MISO-Pad18)") (class "Default")
      (node (ref "U1") (pin "18") (pinfunction "MISO_18") (pintype "bidirectional"))
    )
    (net (code "122") (name "unconnected-(U1-MOSI-Pad17)") (class "Default")
      (node (ref "U1") (pin "17") (pinfunction "MOSI_17") (pintype "bidirectional"))
    )
    (net (code "123") (name "unconnected-(U1-NC-Pad14)") (class "Default")
      (node (ref "U1") (pin "14") (pinfunction "NC_14") (pintype "bidirectional"))
    )
    (net (code "124") (name "unconnected-(U1-PCM_CLK-Pad5)") (class "Default")
      (node (ref "U1") (pin "5") (pinfunction "PCM_CLK_5") (pintype "bidirectional"))
    )
    (net (code "125") (name "unconnected-(U1-PCM_IN-Pad7)") (class "Default")
      (node (ref "U1") (pin "7") (pinfunction "PCM_IN_7") (pintype "bidirectional"))
    )
    (net (code "126") (name "unconnected-(U1-PCM_OUT-Pad6)") (class "Default")
      (node (ref "U1") (pin "6") (pinfunction "PCM_OUT_6") (pintype "bidirectional"))
    )
    (net (code "127") (name "unconnected-(U1-PCN_SYNC-Pad8)") (class "Default")
      (node (ref "U1") (pin "8") (pinfunction "PCN_SYNC_8") (pintype "bidirectional"))
    )
    (net (code "128") (name "unconnected-(U1-PIO0-Pad23)") (class "Default")
      (node (ref "U1") (pin "23") (pinfunction "PIO0_23") (pintype "bidirectional"))
    )
    (net (code "129") (name "unconnected-(U1-PIO1-Pad24)") (class "Default")
      (node (ref "U1") (pin "24") (pinfunction "PIO1_24") (pintype "bidirectional"))
    )
    (net (code "130") (name "unconnected-(U1-PIO2-Pad25)") (class "Default")
      (node (ref "U1") (pin "25") (pinfunction "PIO2_25") (pintype "bidirectional"))
    )
    (net (code "131") (name "unconnected-(U1-PIO3-Pad26)") (class "Default")
      (node (ref "U1") (pin "26") (pinfunction "PIO3_26") (pintype "bidirectional"))
    )
    (net (code "132") (name "unconnected-(U1-PIO4-Pad27)") (class "Default")
      (node (ref "U1") (pin "27") (pinfunction "PIO4_27") (pintype "bidirectional"))
    )
    (net (code "133") (name "unconnected-(U1-PIO5-Pad28)") (class "Default")
      (node (ref "U1") (pin "28") (pinfunction "PIO5_28") (pintype "bidirectional"))
    )
    (net (code "134") (name "unconnected-(U1-PIO6-Pad29)") (class "Default")
      (node (ref "U1") (pin "29") (pinfunction "PIO6_29") (pintype "bidirectional"))
    )
    (net (code "135") (name "unconnected-(U1-PIO7-Pad30)") (class "Default")
      (node (ref "U1") (pin "30") (pinfunction "PIO7_30") (pintype "bidirectional"))
    )
    (net (code "136") (name "unconnected-(U1-PIO9-Pad32)") (class "Default")
      (node (ref "U1") (pin "32") (pinfunction "PIO9_32") (pintype "bidirectional"))
    )
    (net (code "137") (name "unconnected-(U1-PIO10-Pad33)") (class "Default")
      (node (ref "U1") (pin "33") (pinfunction "PIO10_33") (pintype "bidirectional"))
    )
    (net (code "138") (name "unconnected-(U1-RST-Pad11)") (class "Default")
      (node (ref "U1") (pin "11") (pinfunction "RST_11") (pintype "bidirectional"))
    )
    (net (code "139") (name "unconnected-(U1-RTS-Pad4)") (class "Default")
      (node (ref "U1") (pin "4") (pinfunction "RTS_4") (pintype "bidirectional"))
    )
    (net (code "140") (name "unconnected-(U1-VBUSD+-Pad20)") (class "Default")
      (node (ref "U1") (pin "20") (pinfunction "VBUSD+_20") (pintype "bidirectional"))
    )
    (net (code "141") (name "unconnected-(U1-VBUSD--Pad15)") (class "Default")
      (node (ref "U1") (pin "15") (pinfunction "VBUSD-_15") (pintype "bidirectional"))
    )
  )
)
